# Timer_Autoradio_FlipFlop.net
KiCad netlist of a schematic drawn in EAGLE
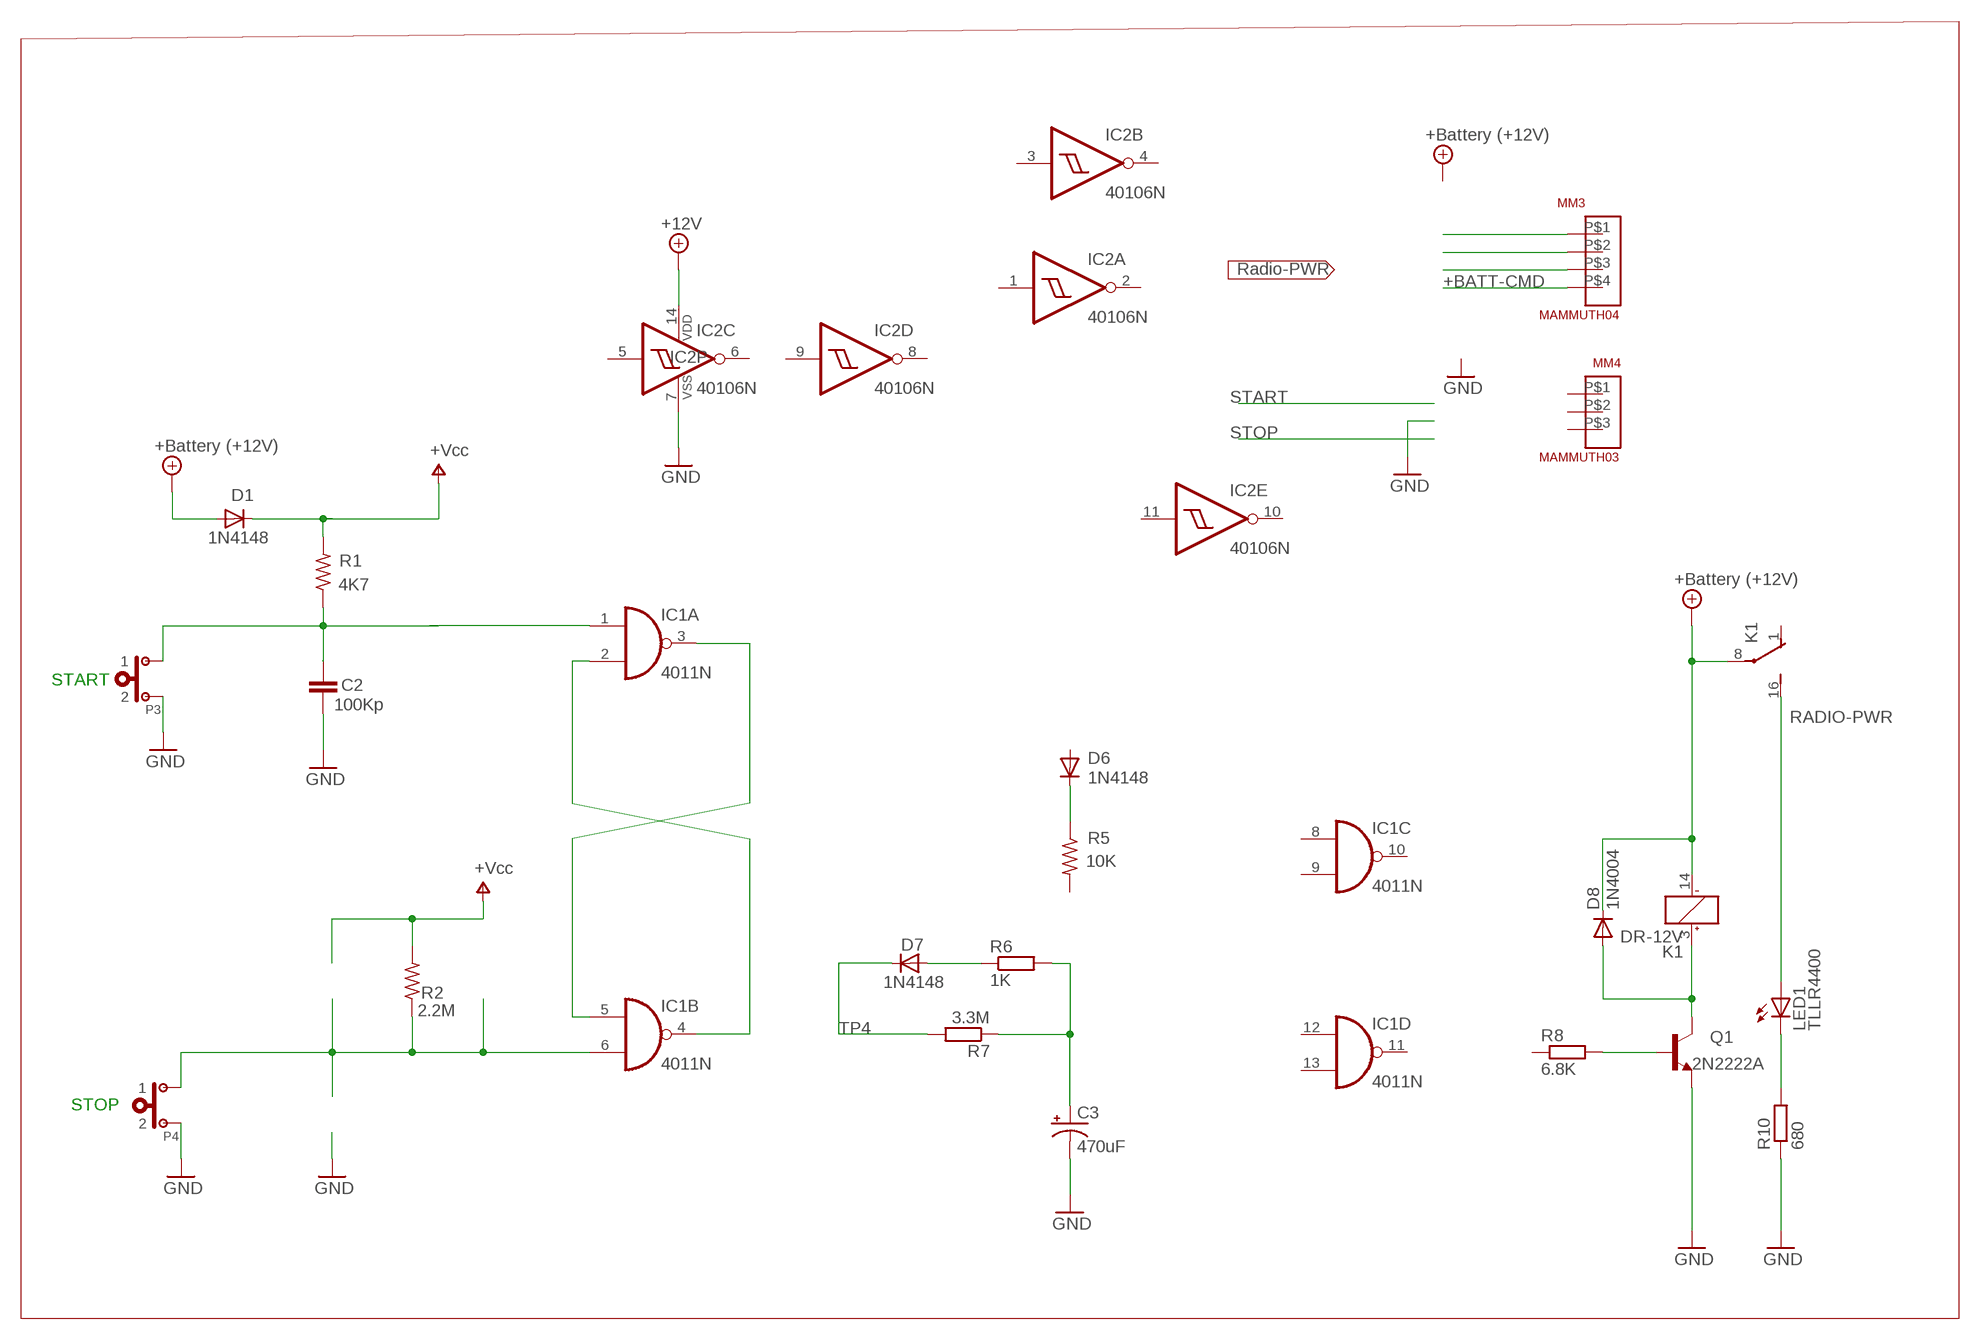
[diagram p0: schematic, sheet 1]

(export (version "E")
  (design (tool "Eeschema 10.0.6"))
  (components
    (comp (ref "C2")
      (value "100Kp")
      (footprint "eagle-import:C025-025X050")
      (libsource (lib "eagle-import") (part "C-EU025-025X050"))
    )
    (comp (ref "C3")
      (value "470uF")
      (footprint "eagle-import:E3,5-8")
      (libsource (lib "eagle-import") (part "CPOL-USE3.5-8"))
    )
    (comp (ref "D1")
      (value "1N4148")
      (footprint "eagle-import:DO35-10")
      (libsource (lib "eagle-import") (part "1N4148DO35-10"))
    )
    (comp (ref "D6")
      (value "1N4148")
      (footprint "eagle-import:DO35-10")
      (libsource (lib "eagle-import") (part "1N4148DO35-10"))
    )
    (comp (ref "D7")
      (value "1N4148")
      (footprint "eagle-import:DO35-10")
      (libsource (lib "eagle-import") (part "1N4148DO35-10"))
    )
    (comp (ref "D8")
      (value "1N4004")
      (footprint "eagle-import:DO41-10")
      (libsource (lib "eagle-import") (part "1N4004"))
    )
    (comp (ref "IC1")
      (value "4011N")
      (footprint "eagle-import:DIL14")
      (libsource (lib "eagle-import") (part "4011N"))
    )
    (comp (ref "IC2")
      (value "40106N")
      (footprint "eagle-import:DIL14")
      (libsource (lib "eagle-import") (part "40106N"))
    )
    (comp (ref "K1")
      (value "DR-12V")
      (footprint "eagle-import:DR-1")
      (libsource (lib "eagle-import") (part "DR-V12"))
    )
    (comp (ref "LED1")
      (value "TLLR4400")
      (footprint "eagle-import:LED3MM")
      (fields (field (name "MF") "VISHAY SEMICONDUCTOR"))
      (libsource (lib "eagle-import") (part "TLLR4400"))
    )
    (comp (ref "MM3")
      (value "MAMMUTH04")
      (footprint "eagle-import:MAMMUTH04")
      (libsource (lib "eagle-import") (part "MAMMUTH04"))
    )
    (comp (ref "MM4")
      (value "MAMMUTH03")
      (footprint "eagle-import:MAMMUTH03")
      (libsource (lib "eagle-import") (part "MAMMUTH03"))
    )
    (comp (ref "P3")
      (value "PULSANTENO")
      (footprint "eagle-import:SIP02")
      (libsource (lib "eagle-import") (part "PULSANTENO"))
    )
    (comp (ref "P4")
      (value "PULSANTENO")
      (footprint "eagle-import:SIP02")
      (libsource (lib "eagle-import") (part "PULSANTENO"))
    )
    (comp (ref "Q1")
      (value "2N2222A")
      (footprint "eagle-import:TO18")
      (libsource (lib "eagle-import") (part "2N2222A"))
    )
    (comp (ref "R1")
      (value "4K7")
      (footprint "eagle-import:0207_12")
      (libsource (lib "eagle-import") (part "R-US_0207/12"))
    )
    (comp (ref "R2")
      (value "2.2M")
      (footprint "eagle-import:0207_12")
      (libsource (lib "eagle-import") (part "R-US_0207/12"))
    )
    (comp (ref "R5")
      (value "10K")
      (footprint "eagle-import:0207_12")
      (libsource (lib "eagle-import") (part "R-US_0207/12"))
    )
    (comp (ref "R6")
      (value "1K")
      (footprint "eagle-import:0207_10")
      (libsource (lib "eagle-import") (part "R-EU_0207/10"))
    )
    (comp (ref "R7")
      (value "3.3M")
      (footprint "eagle-import:0207_10")
      (libsource (lib "eagle-import") (part "R-EU_0207/10"))
    )
    (comp (ref "R8")
      (value "6.8K")
      (footprint "eagle-import:0207_10")
      (libsource (lib "eagle-import") (part "R-EU_0207/10"))
    )
    (comp (ref "R10")
      (value "680")
      (footprint "eagle-import:0207_10")
      (libsource (lib "eagle-import") (part "R-EU_0207/10"))
    )
  )
  (nets
    (net (code "1") (name "+12V") (class "Default")
      (node (ref "D1") (pin "A") (pinfunction "A_A") (pintype "passive"))
      (node (ref "D8") (pin "C") (pinfunction "C_C") (pintype "passive"))
      (node (ref "IC2") (pin "14") (pinfunction "VDD_14") (pintype "power_in"))
      (node (ref "K1") (pin "14") (pinfunction "-_14") (pintype "passive"))
      (node (ref "K1") (pin "8") (pinfunction "P_8") (pintype "passive"))
    )
    (net (code "2") (name "+Vcc") (class "Default")
      (node (ref "D1") (pin "C") (pinfunction "C_C") (pintype "passive"))
      (node (ref "R1") (pin "2") (pinfunction "2_2") (pintype "passive"))
      (node (ref "R2") (pin "2") (pinfunction "2_2") (pintype "passive"))
    )
    (net (code "4") (name "/RADIO-PWR") (class "Default")
      (node (ref "K1") (pin "16") (pinfunction "S_16") (pintype "passive"))
      (node (ref "LED1") (pin "A") (pinfunction "A_A") (pintype "passive"))
    )
    (net (code "5") (name "/START") (class "Default")
      (node (ref "D7") (pin "A") (pinfunction "A_A") (pintype "passive"))
      (node (ref "R6") (pin "1") (pinfunction "1_1") (pintype "passive"))
    )
    (net (code "6") (name "/STOP") (class "Default")
      (node (ref "C2") (pin "1") (pinfunction "1_1") (pintype "passive"))
      (node (ref "IC1") (pin "1") (pinfunction "I0_1") (pintype "input"))
      (node (ref "P3") (pin "1") (pinfunction "1_1") (pintype "bidirectional"))
      (node (ref "R1") (pin "1") (pinfunction "1_1") (pintype "passive"))
    )
    (net (code "7") (name "/TP4") (class "Default")
      (node (ref "D7") (pin "C") (pinfunction "C_C") (pintype "passive"))
      (node (ref "R7") (pin "2") (pinfunction "2_2") (pintype "passive"))
    )
    (net (code "8") (name "GND") (class "Default")
      (node (ref "C3") (pin "-") (pinfunction "-_-") (pintype "passive"))
      (node (ref "IC2") (pin "7") (pinfunction "VSS_7") (pintype "power_in"))
      (node (ref "P3") (pin "2") (pinfunction "2_2") (pintype "bidirectional"))
      (node (ref "P4") (pin "2") (pinfunction "2_2") (pintype "bidirectional"))
      (node (ref "Q1") (pin "1") (pinfunction "E_1") (pintype "passive"))
      (node (ref "R10") (pin "1") (pinfunction "1_1") (pintype "passive"))
    )
    (net (code "9") (name "Net-(C3-Pad+)") (class "Default")
      (node (ref "C3") (pin "+") (pinfunction "+_+") (pintype "passive"))
      (node (ref "R6") (pin "2") (pinfunction "2_2") (pintype "passive"))
      (node (ref "R7") (pin "1") (pinfunction "1_1") (pintype "passive"))
    )
    (net (code "10") (name "Net-(D6-PadC)") (class "Default")
      (node (ref "D6") (pin "C") (pinfunction "C_C") (pintype "passive"))
      (node (ref "R5") (pin "1") (pinfunction "1_1") (pintype "passive"))
    )
    (net (code "11") (name "Net-(IC1A-I1)") (class "Default")
      (node (ref "IC1") (pin "2") (pinfunction "I1_2") (pintype "input"))
      (node (ref "IC1") (pin "4") (pinfunction "O_4") (pintype "output"))
    )
    (net (code "12") (name "Net-(IC1A-O)") (class "Default")
      (node (ref "IC1") (pin "3") (pinfunction "O_3") (pintype "output"))
      (node (ref "IC1") (pin "5") (pinfunction "I0_5") (pintype "input"))
    )
    (net (code "13") (name "Net-(IC1B-I1)") (class "Default")
      (node (ref "IC1") (pin "6") (pinfunction "I1_6") (pintype "input"))
      (node (ref "P4") (pin "1") (pinfunction "1_1") (pintype "bidirectional"))
      (node (ref "R2") (pin "1") (pinfunction "1_1") (pintype "passive"))
    )
    (net (code "14") (name "Net-(K1A-+)") (class "Default")
      (node (ref "D8") (pin "A") (pinfunction "A_A") (pintype "passive"))
      (node (ref "K1") (pin "3") (pinfunction "+_3") (pintype "passive"))
      (node (ref "Q1") (pin "3") (pinfunction "C_3") (pintype "passive"))
    )
    (net (code "15") (name "Net-(LED1-C)") (class "Default")
      (node (ref "LED1") (pin "K") (pinfunction "C_K") (pintype "passive"))
      (node (ref "R10") (pin "2") (pinfunction "2_2") (pintype "passive"))
    )
    (net (code "16") (name "Net-(Q1-B)") (class "Default")
      (node (ref "Q1") (pin "2") (pinfunction "B_2") (pintype "passive"))
      (node (ref "R8") (pin "2") (pinfunction "2_2") (pintype "passive"))
    )
    (net (code "17") (name "unconnected-(C2-Pad2)") (class "Default")
      (node (ref "C2") (pin "2") (pinfunction "2_2") (pintype "passive"))
    )
    (net (code "18") (name "unconnected-(D6-PadA)") (class "Default")
      (node (ref "D6") (pin "A") (pinfunction "A_A") (pintype "passive"))
    )
    (net (code "19") (name "unconnected-(IC1C-I0-Pad8)") (class "Default")
      (node (ref "IC1") (pin "8") (pinfunction "I0_8") (pintype "input"))
    )
    (net (code "20") (name "unconnected-(IC1C-I1-Pad9)") (class "Default")
      (node (ref "IC1") (pin "9") (pinfunction "I1_9") (pintype "input"))
    )
    (net (code "21") (name "unconnected-(IC1C-O-Pad10)") (class "Default")
      (node (ref "IC1") (pin "10") (pinfunction "O_10") (pintype "output"))
    )
    (net (code "22") (name "unconnected-(IC1D-I0-Pad12)") (class "Default")
      (node (ref "IC1") (pin "12") (pinfunction "I0_12") (pintype "input"))
    )
    (net (code "23") (name "unconnected-(IC1D-I1-Pad13)") (class "Default")
      (node (ref "IC1") (pin "13") (pinfunction "I1_13") (pintype "input"))
    )
    (net (code "24") (name "unconnected-(IC1D-O-Pad11)") (class "Default")
      (node (ref "IC1") (pin "11") (pinfunction "O_11") (pintype "output"))
    )
    (net (code "25") (name "unconnected-(IC2A-I-Pad1)") (class "Default")
      (node (ref "IC2") (pin "1") (pinfunction "I_1") (pintype "input"))
    )
    (net (code "26") (name "unconnected-(IC2A-O-Pad2)") (class "Default")
      (node (ref "IC2") (pin "2") (pinfunction "O_2") (pintype "output"))
    )
    (net (code "27") (name "unconnected-(IC2B-I-Pad3)") (class "Default")
      (node (ref "IC2") (pin "3") (pinfunction "I_3") (pintype "input"))
    )
    (net (code "28") (name "unconnected-(IC2B-O-Pad4)") (class "Default")
      (node (ref "IC2") (pin "4") (pinfunction "O_4") (pintype "output"))
    )
    (net (code "29") (name "unconnected-(IC2C-I-Pad5)") (class "Default")
      (node (ref "IC2") (pin "5") (pinfunction "I_5") (pintype "input"))
    )
    (net (code "30") (name "unconnected-(IC2C-O-Pad6)") (class "Default")
      (node (ref "IC2") (pin "6") (pinfunction "O_6") (pintype "output"))
    )
    (net (code "31") (name "unconnected-(IC2D-I-Pad9)") (class "Default")
      (node (ref "IC2") (pin "9") (pinfunction "I_9") (pintype "input"))
    )
    (net (code "32") (name "unconnected-(IC2D-O-Pad8)") (class "Default")
      (node (ref "IC2") (pin "8") (pinfunction "O_8") (pintype "output"))
    )
    (net (code "33") (name "unconnected-(IC2E-I-Pad11)") (class "Default")
      (node (ref "IC2") (pin "11") (pinfunction "I_11") (pintype "input"))
    )
    (net (code "34") (name "unconnected-(IC2E-O-Pad10)") (class "Default")
      (node (ref "IC2") (pin "10") (pinfunction "O_10") (pintype "output"))
    )
    (net (code "35") (name "unconnected-(K1B-O-Pad1)") (class "Default")
      (node (ref "K1") (pin "1") (pinfunction "O_1") (pintype "passive"))
    )
    (net (code "36") (name "unconnected-(MM3-PadP$1)") (class "Default")
      (node (ref "MM3") (pin "P$1") (pinfunction "P$1_P$1") (pintype "bidirectional"))
    )
    (net (code "37") (name "unconnected-(MM3-PadP$2)") (class "Default")
      (node (ref "MM3") (pin "P$2") (pinfunction "P$2_P$2") (pintype "bidirectional"))
    )
    (net (code "38") (name "unconnected-(MM3-PadP$3)") (class "Default")
      (node (ref "MM3") (pin "P$3") (pinfunction "P$3_P$3") (pintype "bidirectional"))
    )
    (net (code "39") (name "unconnected-(MM3-PadP$4)") (class "Default")
      (node (ref "MM3") (pin "P$4") (pinfunction "P$4_P$4") (pintype "bidirectional"))
    )
    (net (code "40") (name "unconnected-(MM4-PadP$1)") (class "Default")
      (node (ref "MM4") (pin "P$1") (pinfunction "P$1_P$1") (pintype "bidirectional"))
    )
    (net (code "41") (name "unconnected-(MM4-PadP$2)") (class "Default")
      (node (ref "MM4") (pin "P$2") (pinfunction "P$2_P$2") (pintype "bidirectional"))
    )
    (net (code "42") (name "unconnected-(MM4-PadP$3)") (class "Default")
      (node (ref "MM4") (pin "P$3") (pinfunction "P$3_P$3") (pintype "bidirectional"))
    )
    (net (code "43") (name "unconnected-(R5-Pad2)") (class "Default")
      (node (ref "R5") (pin "2") (pinfunction "2_2") (pintype "passive"))
    )
    (net (code "44") (name "unconnected-(R8-Pad1)") (class "Default")
      (node (ref "R8") (pin "1") (pinfunction "1_1") (pintype "passive"))
    )
  )
)
